# Instrumentation_amp.net
KiCad netlist of a schematic drawn in EAGLE
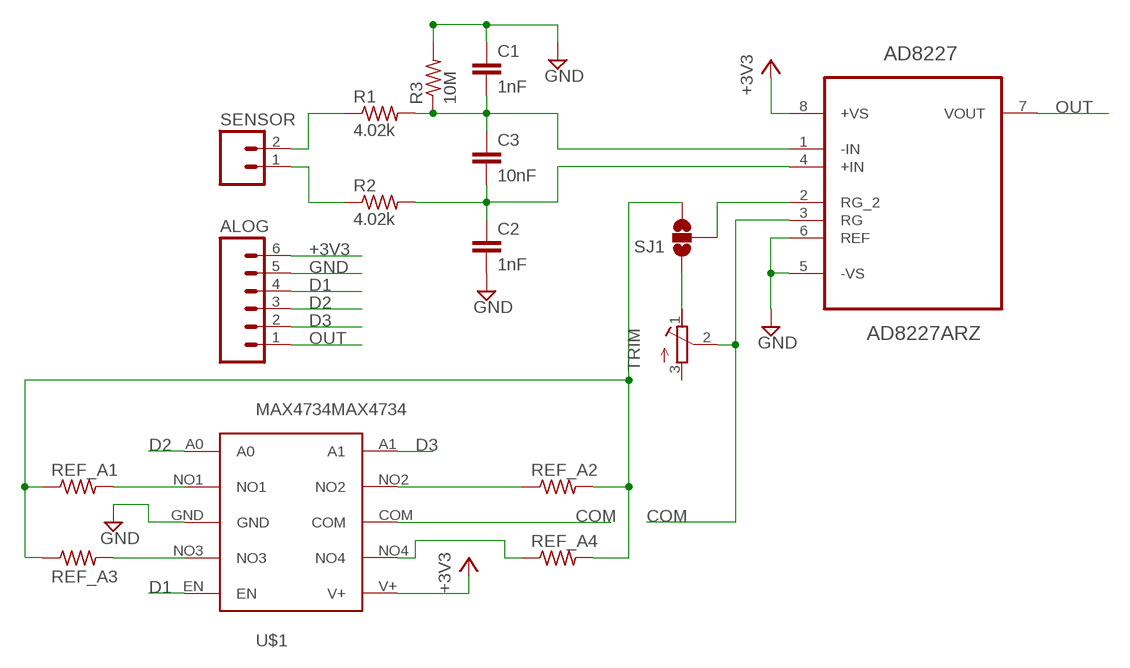
[diagram p0: schematic, sheet 1]

(export (version "E")
  (design (tool "Eeschema 10.0.6"))
  (components
    (comp (ref "AD8227")
      (value "AD8227ARZ")
      (footprint "eagle-import:SOIC127P600X175-8N")
      (libsource (lib "eagle-import") (part "AD8227ARZ"))
    )
    (comp (ref "ALOG")
      (value "M063.5MM-6")
      (footprint "eagle-import:SCREWTERMINAL-3.5MM-6")
      (libsource (lib "eagle-import") (part "M063.5MM-6"))
    )
    (comp (ref "C1")
      (value "1nF")
      (footprint "eagle-import:C0805")
      (libsource (lib "eagle-import") (part "C-EUC0805"))
    )
    (comp (ref "C2")
      (value "1nF")
      (footprint "eagle-import:C0805")
      (libsource (lib "eagle-import") (part "C-EUC0805"))
    )
    (comp (ref "C3")
      (value "10nF")
      (footprint "eagle-import:C0805")
      (libsource (lib "eagle-import") (part "C-EUC0805"))
    )
    (comp (ref "R1")
      (value "4.02k")
      (footprint "eagle-import:M0805")
      (libsource (lib "eagle-import") (part "R-US_M0805"))
    )
    (comp (ref "R2")
      (value "4.02k")
      (footprint "eagle-import:M0805")
      (libsource (lib "eagle-import") (part "R-US_M0805"))
    )
    (comp (ref "R3")
      (value "10M")
      (footprint "eagle-import:M0805")
      (libsource (lib "eagle-import") (part "R-US_M0805"))
    )
    (comp (ref "REF_A1")
      (value "R-US_0207/10")
      (footprint "eagle-import:0207_10")
      (libsource (lib "eagle-import") (part "resistor_R-US_0207/10"))
    )
    (comp (ref "REF_A2")
      (value "R-US_0207/10")
      (footprint "eagle-import:0207_10")
      (libsource (lib "eagle-import") (part "resistor_R-US_0207/10"))
    )
    (comp (ref "REF_A3")
      (value "R-US_0207/10")
      (footprint "eagle-import:0207_10")
      (libsource (lib "eagle-import") (part "resistor_R-US_0207/10"))
    )
    (comp (ref "REF_A4")
      (value "R-US_0207/10")
      (footprint "eagle-import:0207_10")
      (libsource (lib "eagle-import") (part "resistor_R-US_0207/10"))
    )
    (comp (ref "SENSOR")
      (value "M023.5MM")
      (footprint "eagle-import:SCREWTERMINAL-3.5MM-2")
      (libsource (lib "eagle-import") (part "M023.5MM"))
    )
    (comp (ref "SJ1")
      (value "SOLDERJUMPER_2WAYS")
      (footprint "eagle-import:SJ_3")
      (libsource (lib "eagle-import") (part "SOLDERJUMPER_2WAYS"))
    )
    (comp (ref "TRIM")
      (value "R-TRIMM3006P")
      (footprint "eagle-import:RTRIM3006P")
      (libsource (lib "eagle-import") (part "R-TRIMM3006P"))
    )
    (comp (ref "U$1")
      (value "MAX4734MAX4734")
      (footprint "eagle-import:UMAX-10")
      (libsource (lib "eagle-import") (part "MAX4734MAX4734"))
    )
  )
  (nets
    (net (code "1") (name "+3V3") (class "Default")
      (node (ref "AD8227") (pin "8") (pinfunction "+VS_8") (pintype "power_in"))
      (node (ref "ALOG") (pin "6") (pinfunction "6_6") (pintype "passive"))
      (node (ref "U$1") (pin "V+") (pinfunction "V+_V+") (pintype "bidirectional"))
    )
    (net (code "2") (name "/COM") (class "Default")
      (node (ref "AD8227") (pin "3") (pinfunction "RG_3") (pintype "passive"))
      (node (ref "TRIM") (pin "2") (pinfunction "S_2") (pintype "passive"))
      (node (ref "U$1") (pin "COM") (pinfunction "COM_COM") (pintype "bidirectional"))
    )
    (net (code "3") (name "/D1") (class "Default")
      (node (ref "ALOG") (pin "4") (pinfunction "4_4") (pintype "passive"))
      (node (ref "U$1") (pin "EN") (pinfunction "EN_EN") (pintype "bidirectional"))
    )
    (net (code "4") (name "/D2") (class "Default")
      (node (ref "ALOG") (pin "3") (pinfunction "3_3") (pintype "passive"))
      (node (ref "U$1") (pin "A0") (pinfunction "A0_A0") (pintype "bidirectional"))
    )
    (net (code "5") (name "/D3") (class "Default")
      (node (ref "ALOG") (pin "2") (pinfunction "2_2") (pintype "passive"))
      (node (ref "U$1") (pin "A1") (pinfunction "A1_A1") (pintype "bidirectional"))
    )
    (net (code "6") (name "/OUT") (class "Default")
      (node (ref "AD8227") (pin "7") (pinfunction "VOUT_7") (pintype "output"))
      (node (ref "ALOG") (pin "1") (pinfunction "1_1") (pintype "passive"))
    )
    (net (code "7") (name "GND") (class "Default")
      (node (ref "AD8227") (pin "5") (pinfunction "-VS_5") (pintype "power_in"))
      (node (ref "AD8227") (pin "6") (pinfunction "REF_6") (pintype "input"))
      (node (ref "ALOG") (pin "5") (pinfunction "5_5") (pintype "passive"))
      (node (ref "C1") (pin "1") (pinfunction "1_1") (pintype "passive"))
      (node (ref "C2") (pin "2") (pinfunction "2_2") (pintype "passive"))
      (node (ref "R3") (pin "2") (pinfunction "2_2") (pintype "passive"))
      (node (ref "U$1") (pin "GND") (pinfunction "GND_GND") (pintype "bidirectional"))
    )
    (net (code "8") (name "Net-(AD8227-+IN)") (class "Default")
      (node (ref "AD8227") (pin "4") (pinfunction "+IN_4") (pintype "input"))
      (node (ref "C2") (pin "1") (pinfunction "1_1") (pintype "passive"))
      (node (ref "C3") (pin "2") (pinfunction "2_2") (pintype "passive"))
      (node (ref "R2") (pin "2") (pinfunction "2_2") (pintype "passive"))
    )
    (net (code "9") (name "Net-(AD8227--IN)") (class "Default")
      (node (ref "AD8227") (pin "1") (pinfunction "-IN_1") (pintype "input"))
      (node (ref "C1") (pin "2") (pinfunction "2_2") (pintype "passive"))
      (node (ref "C3") (pin "1") (pinfunction "1_1") (pintype "passive"))
      (node (ref "R1") (pin "2") (pinfunction "2_2") (pintype "passive"))
      (node (ref "R3") (pin "1") (pinfunction "1_1") (pintype "passive"))
    )
    (net (code "10") (name "Net-(AD8227-RG_2)") (class "Default")
      (node (ref "AD8227") (pin "2") (pinfunction "RG_2_2") (pintype "passive"))
      (node (ref "SJ1") (pin "2") (pinfunction "2_2") (pintype "passive"))
    )
    (net (code "11") (name "Net-(R1-Pad1)") (class "Default")
      (node (ref "R1") (pin "1") (pinfunction "1_1") (pintype "passive"))
      (node (ref "SENSOR") (pin "2") (pinfunction "2_2") (pintype "passive"))
    )
    (net (code "12") (name "Net-(R2-Pad1)") (class "Default")
      (node (ref "R2") (pin "1") (pinfunction "1_1") (pintype "passive"))
      (node (ref "SENSOR") (pin "1") (pinfunction "1_1") (pintype "passive"))
    )
    (net (code "13") (name "Net-(REF_A1-Pad1)") (class "Default")
      (node (ref "REF_A1") (pin "1") (pinfunction "1_1") (pintype "passive"))
      (node (ref "REF_A2") (pin "2") (pinfunction "2_2") (pintype "passive"))
      (node (ref "REF_A3") (pin "1") (pinfunction "1_1") (pintype "passive"))
      (node (ref "REF_A4") (pin "2") (pinfunction "2_2") (pintype "passive"))
      (node (ref "SJ1") (pin "3") (pinfunction "3_3") (pintype "passive"))
    )
    (net (code "14") (name "Net-(REF_A1-Pad2)") (class "Default")
      (node (ref "REF_A1") (pin "2") (pinfunction "2_2") (pintype "passive"))
      (node (ref "U$1") (pin "NO1") (pinfunction "NO1_NO1") (pintype "bidirectional"))
    )
    (net (code "15") (name "Net-(REF_A2-Pad1)") (class "Default")
      (node (ref "REF_A2") (pin "1") (pinfunction "1_1") (pintype "passive"))
      (node (ref "U$1") (pin "NO2") (pinfunction "NO2_NO2") (pintype "bidirectional"))
    )
    (net (code "16") (name "Net-(REF_A3-Pad2)") (class "Default")
      (node (ref "REF_A3") (pin "2") (pinfunction "2_2") (pintype "passive"))
      (node (ref "U$1") (pin "NO3") (pinfunction "NO3_NO3") (pintype "bidirectional"))
    )
    (net (code "17") (name "Net-(REF_A4-Pad1)") (class "Default")
      (node (ref "REF_A4") (pin "1") (pinfunction "1_1") (pintype "passive"))
      (node (ref "U$1") (pin "NO4") (pinfunction "NO4_NO4") (pintype "bidirectional"))
    )
    (net (code "18") (name "Net-(TRIM-A)") (class "Default")
      (node (ref "SJ1") (pin "1") (pinfunction "1_1") (pintype "passive"))
      (node (ref "TRIM") (pin "1") (pinfunction "A_1") (pintype "passive"))
    )
    (net (code "19") (name "unconnected-(TRIM-E-Pad3)") (class "Default")
      (node (ref "TRIM") (pin "3") (pinfunction "E_3") (pintype "passive"))
    )
  )
)
